# Addon-mapleCUx_Raspi-3V3-UART-CC2530-V02.net
KiCad netlist of a schematic drawn in EAGLE
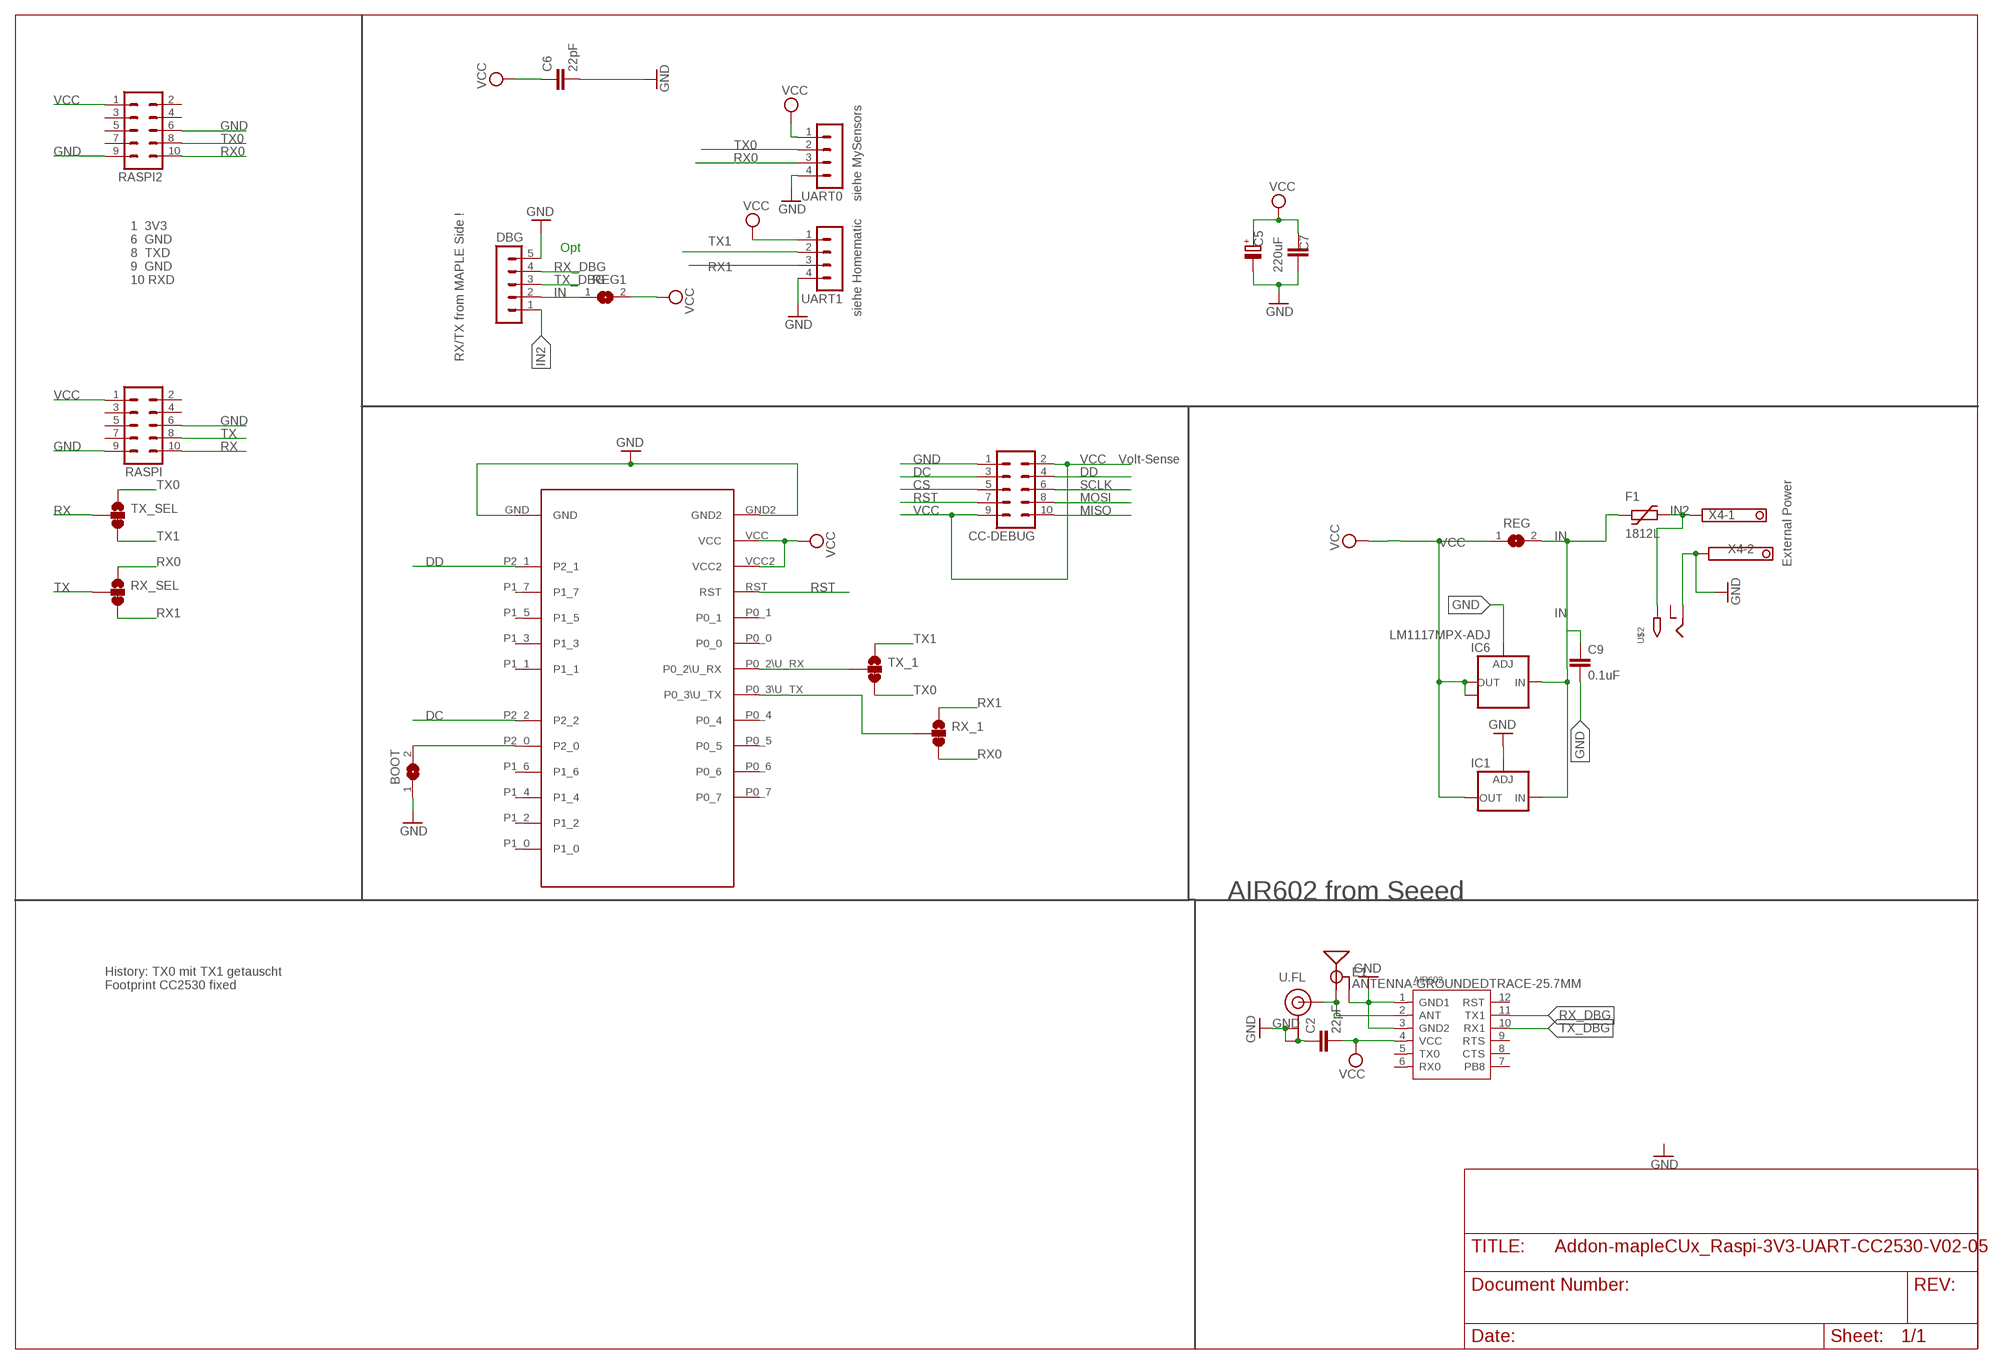
[diagram p0: schematic, sheet 1]

(export (version "E")
  (design (tool "Eeschema 10.0.6"))
  (components
    (comp (ref "AIR602")
      (value "AIR602")
      (footprint "eagle-import:MODULE12P-2.0-10X12MM")
      (libsource (lib "eagle-import") (part "AIR602"))
    )
    (comp (ref "BOOT")
      (value "SJ")
      (footprint "eagle-import:SJ")
      (libsource (lib "eagle-import") (part "SJ"))
    )
    (comp (ref "C2")
      (value "22pF")
      (footprint "eagle-import:C0805")
      (libsource (lib "eagle-import") (part "C-EUC0805"))
    )
    (comp (ref "C5")
      (value "220uF")
      (footprint "eagle-import:E5-8,5")
      (libsource (lib "eagle-import") (part "CPOL-EUE5-8.5"))
    )
    (comp (ref "C6")
      (value "22pF")
      (footprint "eagle-import:C0805")
      (libsource (lib "eagle-import") (part "rcl_334_C-EUC0805"))
    )
    (comp (ref "C7")
      (value "C-EUC1812")
      (footprint "eagle-import:C1812")
      (libsource (lib "eagle-import") (part "rcl_334_C-EUC1812"))
    )
    (comp (ref "C9")
      (value "0.1uF")
      (footprint "eagle-import:C1206")
      (libsource (lib "eagle-import") (part "rcl_334_C-EUC1206"))
    )
    (comp (ref "CC-DEBUG")
      (value "MA05-2")
      (footprint "eagle-import:MA05-2")
      (libsource (lib "eagle-import") (part "MA05-2"))
    )
    (comp (ref "DBG")
      (value "MA05-1")
      (footprint "eagle-import:MA05-1")
      (libsource (lib "eagle-import") (part "MA05-1"))
    )
    (comp (ref "E1")
      (value "ANTENNA-GROUNDEDTRACE-25.7MM")
      (footprint "eagle-import:TRACE_ANTENNA_2.4GHZ_25.7MM")
      (libsource (lib "eagle-import") (part "ANTENNA-GROUNDEDTRACE-25.7MM"))
    )
    (comp (ref "F1")
      (value "1812L")
      (footprint "eagle-import:1812L")
      (libsource (lib "eagle-import") (part "1812L"))
    )
    (comp (ref "IC1")
      (value "LD117ADT50TR")
      (footprint "eagle-import:DPACK")
      (libsource (lib "eagle-import") (part "LD117A?DT50TR"))
    )
    (comp (ref "IC6")
      (value "LM1117MPX-ADJ")
      (footprint "eagle-import:SOT223")
      (libsource (lib "eagle-import") (part "LM1117MPX-ADJ"))
    )
    (comp (ref "RASPI")
      (value "MA05-2")
      (footprint "eagle-import:MA05-2")
      (libsource (lib "eagle-import") (part "MA05-2"))
    )
    (comp (ref "RASPI2")
      (value "MA05-2")
      (footprint "eagle-import:MA05-2")
      (libsource (lib "eagle-import") (part "MA05-2"))
    )
    (comp (ref "REG") (value "SJ") (footprint "eagle-import:SJ") (libsource (lib "eagle-import") (part "SJ")))
    (comp (ref "REG1")
      (value "SJ")
      (footprint "eagle-import:SJ")
      (libsource (lib "eagle-import") (part "SJ"))
    )
    (comp (ref "RX_1")
      (value "JUMPER-SMT_3_1-NC_TRACE_SILK")
      (footprint "eagle-import:SMT-JUMPER_3_1-NC_TRACE_SILK")
      (libsource (lib "eagle-import") (part "JUMPER-SMT_3_1-NC_TRACE_SILK"))
    )
    (comp (ref "RX_SEL")
      (value "JUMPER-SMT_3_1-NC_TRACE_SILK")
      (footprint "eagle-import:SMT-JUMPER_3_1-NC_TRACE_SILK")
      (libsource (lib "eagle-import") (part "JUMPER-SMT_3_1-NC_TRACE_SILK"))
    )
    (comp (ref "TX_1")
      (value "JUMPER-SMT_3_1-NC_TRACE_SILK")
      (footprint "eagle-import:SMT-JUMPER_3_1-NC_TRACE_SILK")
      (libsource (lib "eagle-import") (part "JUMPER-SMT_3_1-NC_TRACE_SILK"))
    )
    (comp (ref "TX_SEL")
      (value "JUMPER-SMT_3_1-NC_TRACE_SILK")
      (footprint "eagle-import:SMT-JUMPER_3_1-NC_TRACE_SILK")
      (libsource (lib "eagle-import") (part "JUMPER-SMT_3_1-NC_TRACE_SILK"))
    )
    (comp (ref "U$2")
      (value "2.1MMJACKTHM")
      (footprint "eagle-import:PJ-102A")
      (libsource (lib "eagle-import") (part "2.1MMJACKTHM"))
    )
    (comp (ref "U$3")
      (value "CC2530_MODULE")
      (footprint "eagle-import:CC2530_DIL")
      (libsource (lib "eagle-import") (part "CC2530_MODULE"))
    )
    (comp (ref "U.FL")
      (value "U.FL")
      (footprint "eagle-import:U.FL")
      (libsource (lib "eagle-import") (part "U.FL"))
    )
    (comp (ref "UART0")
      (value "MA04-1")
      (footprint "eagle-import:MA04-1")
      (libsource (lib "eagle-import") (part "MA04-1"))
    )
    (comp (ref "UART1")
      (value "MA04-1")
      (footprint "eagle-import:MA04-1")
      (libsource (lib "eagle-import") (part "MA04-1"))
    )
    (comp (ref "X4")
      (value "1751248")
      (footprint "eagle-import:1751248")
      (libsource (lib "eagle-import") (part "1751248"))
    )
  )
  (nets
    (net (code "1") (name "/CS") (class "Default")
      (node (ref "CC-DEBUG") (pin "5") (pinfunction "5_5") (pintype "passive"))
    )
    (net (code "2") (name "/DC") (class "Default")
      (node (ref "CC-DEBUG") (pin "3") (pinfunction "3_3") (pintype "passive"))
      (node (ref "U$3") (pin "P2_2") (pinfunction "P2_2_P2_2") (pintype "bidirectional"))
    )
    (net (code "3") (name "/DD") (class "Default")
      (node (ref "CC-DEBUG") (pin "4") (pinfunction "4_4") (pintype "passive"))
      (node (ref "U$3") (pin "P2_1") (pinfunction "P2_1_P2_1") (pintype "bidirectional"))
    )
    (net (code "4") (name "/IN") (class "Default")
      (node (ref "C9") (pin "1") (pinfunction "1_1") (pintype "passive"))
      (node (ref "DBG") (pin "2") (pinfunction "2_2") (pintype "passive"))
      (node (ref "F1") (pin "P$1") (pinfunction "1_P$1") (pintype "passive"))
      (node (ref "IC1") (pin "3") (pinfunction "IN_3") (pintype "input"))
      (node (ref "IC6") (pin "3") (pinfunction "IN_3") (pintype "input"))
      (node (ref "REG") (pin "2") (pinfunction "2_2") (pintype "passive"))
      (node (ref "REG1") (pin "1") (pinfunction "1_1") (pintype "passive"))
    )
    (net (code "5") (name "/MISO") (class "Default")
      (node (ref "CC-DEBUG") (pin "10") (pinfunction "10_10") (pintype "passive"))
    )
    (net (code "6") (name "/MOSI") (class "Default")
      (node (ref "CC-DEBUG") (pin "8") (pinfunction "8_8") (pintype "passive"))
    )
    (net (code "7") (name "/RST") (class "Default")
      (node (ref "CC-DEBUG") (pin "7") (pinfunction "7_7") (pintype "passive"))
      (node (ref "U$3") (pin "RST") (pinfunction "RST_RST") (pintype "bidirectional"))
    )
    (net (code "8") (name "/RX") (class "Default")
      (node (ref "RASPI") (pin "10") (pinfunction "10_10") (pintype "passive"))
      (node (ref "TX_SEL") (pin "2") (pinfunction "2_2") (pintype "passive"))
    )
    (net (code "9") (name "/RX0") (class "Default")
      (node (ref "RASPI2") (pin "10") (pinfunction "10_10") (pintype "passive"))
      (node (ref "RX_1") (pin "3") (pinfunction "3_3") (pintype "passive"))
      (node (ref "RX_SEL") (pin "1") (pinfunction "1_1") (pintype "passive"))
      (node (ref "UART0") (pin "3") (pinfunction "3_3") (pintype "passive"))
    )
    (net (code "10") (name "/RX1") (class "Default")
      (node (ref "RX_1") (pin "1") (pinfunction "1_1") (pintype "passive"))
      (node (ref "RX_SEL") (pin "3") (pinfunction "3_3") (pintype "passive"))
      (node (ref "UART1") (pin "3") (pinfunction "3_3") (pintype "passive"))
    )
    (net (code "11") (name "/SCLK") (class "Default")
      (node (ref "CC-DEBUG") (pin "6") (pinfunction "6_6") (pintype "passive"))
    )
    (net (code "12") (name "/TX") (class "Default")
      (node (ref "RASPI") (pin "8") (pinfunction "8_8") (pintype "passive"))
      (node (ref "RX_SEL") (pin "2") (pinfunction "2_2") (pintype "passive"))
    )
    (net (code "13") (name "/TX0") (class "Default")
      (node (ref "RASPI2") (pin "8") (pinfunction "8_8") (pintype "passive"))
      (node (ref "TX_1") (pin "3") (pinfunction "3_3") (pintype "passive"))
      (node (ref "TX_SEL") (pin "1") (pinfunction "1_1") (pintype "passive"))
      (node (ref "UART0") (pin "2") (pinfunction "2_2") (pintype "passive"))
    )
    (net (code "14") (name "/TX1") (class "Default")
      (node (ref "TX_1") (pin "1") (pinfunction "1_1") (pintype "passive"))
      (node (ref "TX_SEL") (pin "3") (pinfunction "3_3") (pintype "passive"))
      (node (ref "UART1") (pin "2") (pinfunction "2_2") (pintype "passive"))
    )
    (net (code "15") (name "GND") (class "Default")
      (node (ref "AIR602") (pin "1") (pinfunction "GND1_1") (pintype "bidirectional"))
      (node (ref "AIR602") (pin "3") (pinfunction "GND2_3") (pintype "bidirectional"))
      (node (ref "BOOT") (pin "1") (pinfunction "1_1") (pintype "passive"))
      (node (ref "C2") (pin "1") (pinfunction "1_1") (pintype "passive"))
      (node (ref "C5") (pin "-") (pinfunction "-_-") (pintype "passive"))
      (node (ref "C6") (pin "2") (pinfunction "2_2") (pintype "passive"))
      (node (ref "C7") (pin "1") (pinfunction "1_1") (pintype "passive"))
      (node (ref "C9") (pin "2") (pinfunction "2_2") (pintype "passive"))
      (node (ref "CC-DEBUG") (pin "1") (pinfunction "1_1") (pintype "passive"))
      (node (ref "DBG") (pin "5") (pinfunction "5_5") (pintype "passive"))
      (node (ref "E1") (pin "GND") (pinfunction "GND_GND") (pintype "bidirectional"))
      (node (ref "E1") (pin "GND2") (pinfunction "GND_GND2") (pintype "bidirectional"))
      (node (ref "IC1") (pin "1") (pinfunction "ADJ_1") (pintype "input"))
      (node (ref "IC6") (pin "1") (pinfunction "ADJ_1") (pintype "input"))
      (node (ref "RASPI") (pin "6") (pinfunction "6_6") (pintype "passive"))
      (node (ref "RASPI") (pin "9") (pinfunction "9_9") (pintype "passive"))
      (node (ref "RASPI2") (pin "6") (pinfunction "6_6") (pintype "passive"))
      (node (ref "RASPI2") (pin "9") (pinfunction "9_9") (pintype "passive"))
      (node (ref "U$2") (pin "RING") (pinfunction "RING_RING") (pintype "bidirectional"))
      (node (ref "U$3") (pin "GND") (pinfunction "GND_GND") (pintype "bidirectional"))
      (node (ref "U$3") (pin "GND2") (pinfunction "GND2_GND2") (pintype "bidirectional"))
      (node (ref "U.FL") (pin "1") (pinfunction "GND_1") (pintype "bidirectional"))
      (node (ref "U.FL") (pin "2") (pinfunction "GND_2") (pintype "bidirectional"))
      (node (ref "UART0") (pin "4") (pinfunction "4_4") (pintype "passive"))
      (node (ref "UART1") (pin "4") (pinfunction "4_4") (pintype "passive"))
      (node (ref "X4") (pin "2") (pinfunction "K_2") (pintype "passive"))
    )
    (net (code "16") (name "IN2") (class "Default")
      (node (ref "DBG") (pin "1") (pinfunction "1_1") (pintype "passive"))
      (node (ref "F1") (pin "P$2") (pinfunction "2_P$2") (pintype "passive"))
      (node (ref "U$2") (pin "TIP") (pinfunction "TIP_TIP") (pintype "bidirectional"))
      (node (ref "X4") (pin "1") (pinfunction "K_1") (pintype "passive"))
    )
    (net (code "17") (name "Net-(AIR602-ANT)") (class "Default")
      (node (ref "AIR602") (pin "2") (pinfunction "ANT_2") (pintype "bidirectional"))
      (node (ref "E1") (pin "ANT") (pinfunction "SIGNAL_ANT") (pintype "bidirectional"))
      (node (ref "U.FL") (pin "FEED") (pinfunction "SIGNAL_FEED") (pintype "bidirectional"))
    )
    (net (code "18") (name "Net-(BOOT-Pad2)") (class "Default")
      (node (ref "BOOT") (pin "2") (pinfunction "2_2") (pintype "passive"))
      (node (ref "U$3") (pin "P2_0") (pinfunction "P2_0_P2_0") (pintype "bidirectional"))
    )
    (net (code "19") (name "Net-(RX_1-Pad2)") (class "Default")
      (node (ref "RX_1") (pin "2") (pinfunction "2_2") (pintype "passive"))
      (node (ref "U$3") (pin "P0_3\\U_TX") (pinfunction "P0_3\\U_TX_P0_3\\U_TX") (pintype "bidirectional"))
    )
    (net (code "20") (name "Net-(TX_1-Pad2)") (class "Default")
      (node (ref "TX_1") (pin "2") (pinfunction "2_2") (pintype "passive"))
      (node (ref "U$3") (pin "P0_2\\U_RX") (pinfunction "P0_2\\U_RX_P0_2\\U_RX") (pintype "bidirectional"))
    )
    (net (code "21") (name "RX_DBG") (class "Default")
      (node (ref "AIR602") (pin "11") (pinfunction "TX1_11") (pintype "bidirectional"))
      (node (ref "DBG") (pin "4") (pinfunction "4_4") (pintype "passive"))
    )
    (net (code "22") (name "TX_DBG") (class "Default")
      (node (ref "AIR602") (pin "10") (pinfunction "RX1_10") (pintype "bidirectional"))
      (node (ref "DBG") (pin "3") (pinfunction "3_3") (pintype "passive"))
    )
    (net (code "23") (name "VCC") (class "Default")
      (node (ref "AIR602") (pin "4") (pinfunction "VCC_4") (pintype "bidirectional"))
      (node (ref "C2") (pin "2") (pinfunction "2_2") (pintype "passive"))
      (node (ref "C5") (pin "+") (pinfunction "+_+") (pintype "passive"))
      (node (ref "C6") (pin "1") (pinfunction "1_1") (pintype "passive"))
      (node (ref "C7") (pin "2") (pinfunction "2_2") (pintype "passive"))
      (node (ref "CC-DEBUG") (pin "2") (pinfunction "2_2") (pintype "passive"))
      (node (ref "CC-DEBUG") (pin "9") (pinfunction "9_9") (pintype "passive"))
      (node (ref "IC1") (pin "4") (pinfunction "OUT_4") (pintype "passive"))
      (node (ref "IC6") (pin "2") (pinfunction "OUT_2") (pintype "passive"))
      (node (ref "IC6") (pin "TAB") (pinfunction "OUT1_TAB") (pintype "passive"))
      (node (ref "RASPI") (pin "1") (pinfunction "1_1") (pintype "passive"))
      (node (ref "RASPI2") (pin "1") (pinfunction "1_1") (pintype "passive"))
      (node (ref "REG") (pin "1") (pinfunction "1_1") (pintype "passive"))
      (node (ref "REG1") (pin "2") (pinfunction "2_2") (pintype "passive"))
      (node (ref "U$3") (pin "VCC") (pinfunction "VCC_VCC") (pintype "bidirectional"))
      (node (ref "U$3") (pin "VCC2") (pinfunction "VCC2_VCC2") (pintype "bidirectional"))
      (node (ref "UART0") (pin "1") (pinfunction "1_1") (pintype "passive"))
      (node (ref "UART1") (pin "1") (pinfunction "1_1") (pintype "passive"))
    )
    (net (code "24") (name "unconnected-(AIR602-CTS-Pad8)") (class "Default")
      (node (ref "AIR602") (pin "8") (pinfunction "CTS_8") (pintype "bidirectional"))
    )
    (net (code "25") (name "unconnected-(AIR602-PB8-Pad7)") (class "Default")
      (node (ref "AIR602") (pin "7") (pinfunction "PB8_7") (pintype "bidirectional"))
    )
    (net (code "26") (name "unconnected-(AIR602-RST-Pad12)") (class "Default")
      (node (ref "AIR602") (pin "12") (pinfunction "RST_12") (pintype "bidirectional"))
    )
    (net (code "27") (name "unconnected-(AIR602-RTS-Pad9)") (class "Default")
      (node (ref "AIR602") (pin "9") (pinfunction "RTS_9") (pintype "bidirectional"))
    )
    (net (code "28") (name "unconnected-(AIR602-RX0-Pad6)") (class "Default")
      (node (ref "AIR602") (pin "6") (pinfunction "RX0_6") (pintype "bidirectional"))
    )
    (net (code "29") (name "unconnected-(AIR602-TX0-Pad5)") (class "Default")
      (node (ref "AIR602") (pin "5") (pinfunction "TX0_5") (pintype "bidirectional"))
    )
    (net (code "30") (name "unconnected-(RASPI-Pad2)") (class "Default")
      (node (ref "RASPI") (pin "2") (pinfunction "2_2") (pintype "passive"))
    )
    (net (code "31") (name "unconnected-(RASPI-Pad3)") (class "Default")
      (node (ref "RASPI") (pin "3") (pinfunction "3_3") (pintype "passive"))
    )
    (net (code "32") (name "unconnected-(RASPI-Pad4)") (class "Default")
      (node (ref "RASPI") (pin "4") (pinfunction "4_4") (pintype "passive"))
    )
    (net (code "33") (name "unconnected-(RASPI-Pad5)") (class "Default")
      (node (ref "RASPI") (pin "5") (pinfunction "5_5") (pintype "passive"))
    )
    (net (code "34") (name "unconnected-(RASPI-Pad7)") (class "Default")
      (node (ref "RASPI") (pin "7") (pinfunction "7_7") (pintype "passive"))
    )
    (net (code "35") (name "unconnected-(RASPI2-Pad2)") (class "Default")
      (node (ref "RASPI2") (pin "2") (pinfunction "2_2") (pintype "passive"))
    )
    (net (code "36") (name "unconnected-(RASPI2-Pad3)") (class "Default")
      (node (ref "RASPI2") (pin "3") (pinfunction "3_3") (pintype "passive"))
    )
    (net (code "37") (name "unconnected-(RASPI2-Pad4)") (class "Default")
      (node (ref "RASPI2") (pin "4") (pinfunction "4_4") (pintype "passive"))
    )
    (net (code "38") (name "unconnected-(RASPI2-Pad5)") (class "Default")
      (node (ref "RASPI2") (pin "5") (pinfunction "5_5") (pintype "passive"))
    )
    (net (code "39") (name "unconnected-(RASPI2-Pad7)") (class "Default")
      (node (ref "RASPI2") (pin "7") (pinfunction "7_7") (pintype "passive"))
    )
    (net (code "40") (name "unconnected-(U$2-PadRING_SW)") (class "Default")
      (node (ref "U$2") (pin "RING_SW") (pinfunction "RING_SW_RING_SW") (pintype "bidirectional"))
    )
    (net (code "41") (name "unconnected-(U$3-PadP0_0)") (class "Default")
      (node (ref "U$3") (pin "P0_0") (pinfunction "P0_0_P0_0") (pintype "bidirectional"))
    )
    (net (code "42") (name "unconnected-(U$3-PadP0_1)") (class "Default")
      (node (ref "U$3") (pin "P0_1") (pinfunction "P0_1_P0_1") (pintype "bidirectional"))
    )
    (net (code "43") (name "unconnected-(U$3-PadP0_4)") (class "Default")
      (node (ref "U$3") (pin "P0_4") (pinfunction "P0_4_P0_4") (pintype "bidirectional"))
    )
    (net (code "44") (name "unconnected-(U$3-PadP0_5)") (class "Default")
      (node (ref "U$3") (pin "P0_5") (pinfunction "P0_5_P0_5") (pintype "bidirectional"))
    )
    (net (code "45") (name "unconnected-(U$3-PadP0_6)") (class "Default")
      (node (ref "U$3") (pin "P0_6") (pinfunction "P0_6_P0_6") (pintype "bidirectional"))
    )
    (net (code "46") (name "unconnected-(U$3-PadP0_7)") (class "Default")
      (node (ref "U$3") (pin "P0_7") (pinfunction "P0_7_P0_7") (pintype "bidirectional"))
    )
    (net (code "47") (name "unconnected-(U$3-PadP1_0)") (class "Default")
      (node (ref "U$3") (pin "P1_0") (pinfunction "P1_0_P1_0") (pintype "bidirectional"))
    )
    (net (code "48") (name "unconnected-(U$3-PadP1_1)") (class "Default")
      (node (ref "U$3") (pin "P1_1") (pinfunction "P1_1_P1_1") (pintype "bidirectional"))
    )
    (net (code "49") (name "unconnected-(U$3-PadP1_2)") (class "Default")
      (node (ref "U$3") (pin "P1_2") (pinfunction "P1_2_P1_2") (pintype "bidirectional"))
    )
    (net (code "50") (name "unconnected-(U$3-PadP1_3)") (class "Default")
      (node (ref "U$3") (pin "P1_3") (pinfunction "P1_3_P1_3") (pintype "bidirectional"))
    )
    (net (code "51") (name "unconnected-(U$3-PadP1_4)") (class "Default")
      (node (ref "U$3") (pin "P1_4") (pinfunction "P1_4_P1_4") (pintype "bidirectional"))
    )
    (net (code "52") (name "unconnected-(U$3-PadP1_5)") (class "Default")
      (node (ref "U$3") (pin "P1_5") (pinfunction "P1_5_P1_5") (pintype "bidirectional"))
    )
    (net (code "53") (name "unconnected-(U$3-PadP1_6)") (class "Default")
      (node (ref "U$3") (pin "P1_6") (pinfunction "P1_6_P1_6") (pintype "bidirectional"))
    )
    (net (code "54") (name "unconnected-(U$3-PadP1_7)") (class "Default")
      (node (ref "U$3") (pin "P1_7") (pinfunction "P1_7_P1_7") (pintype "bidirectional"))
    )
  )
)
